# rapidshark-motor-connector-mk-1_0.net
KiCad netlist of a schematic drawn in EAGLE
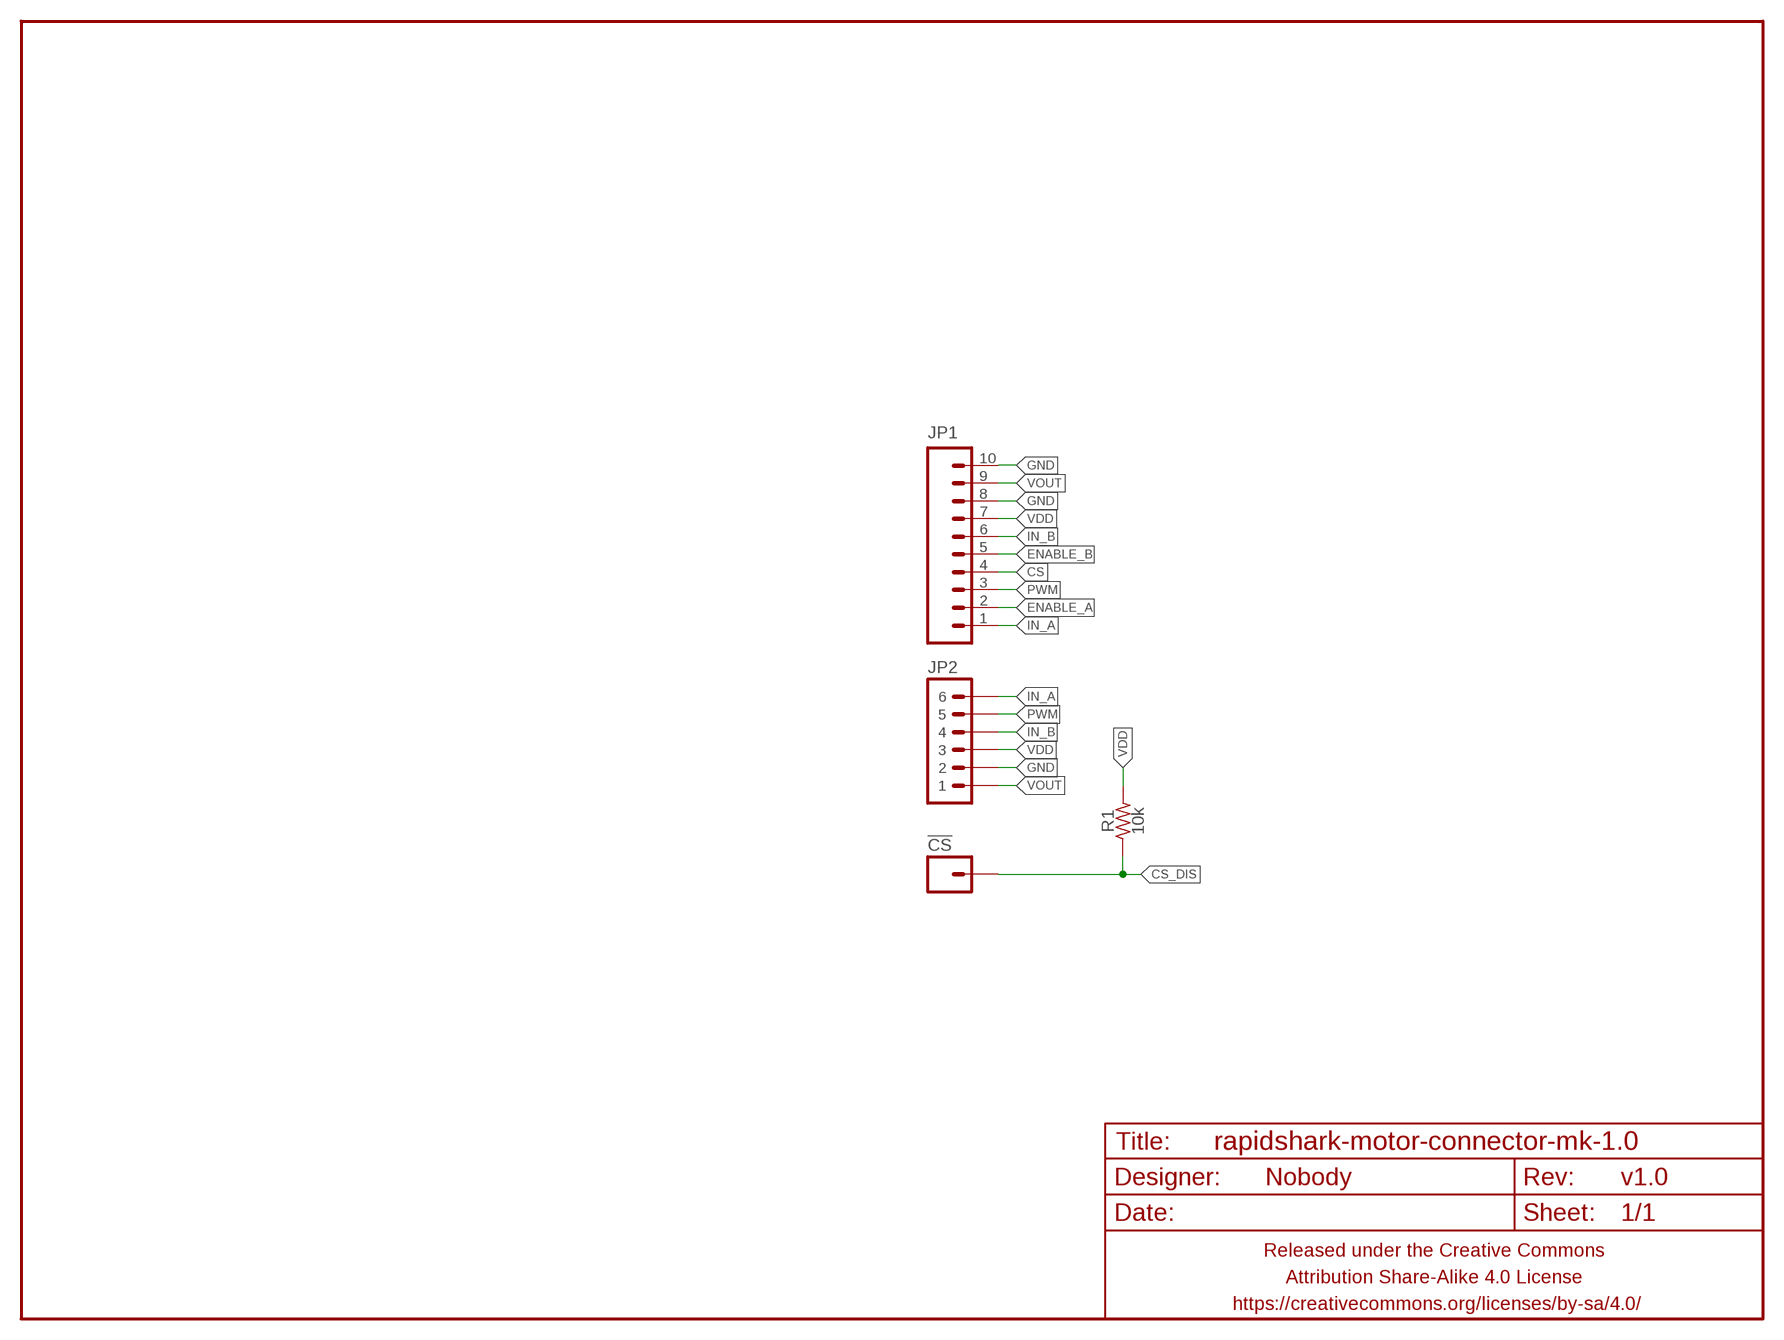
[diagram p0: schematic, sheet 1]

(export (version "E")
  (design (tool "Eeschema 10.0.6"))
  (components
    (comp (ref "!CS")
      (value "M01PTH")
      (footprint "eagle-import:1X01")
      (libsource (lib "eagle-import") (part "M01PTH"))
    )
    (comp (ref "FRAME1")
      (value "FRAME-LETTERNO_PACKAGE")
      (footprint "eagle-import:DUMMY")
      (fields (field (name "VERSION") "v1.0") (field (name "DESIGNER") "Nobody"))
      (libsource (lib "eagle-import") (part "FRAME-LETTERNO_PACKAGE"))
    )
    (comp (ref "JP1")
      (value "M10PTH")
      (footprint "eagle-import:1X10")
      (libsource (lib "eagle-import") (part "M10PTH"))
    )
    (comp (ref "JP2")
      (value "M06JST-PH-PTH-RA")
      (footprint "eagle-import:JST-6-PH-RA-PTH")
      (libsource (lib "eagle-import") (part "M06JST-PH-PTH-RA"))
    )
    (comp (ref "R1")
      (value "10k")
      (footprint "eagle-import:RESISTOR-AXIAL-PTH-6.35MM")
      (libsource (lib "eagle-import") (part "RESISTORPTH-AXIAL-6.35MM"))
    )
  )
  (nets
    (net (code "1") (name "CS") (class "Default")
      (node (ref "JP1") (pin "4") (pinfunction "4_4") (pintype "passive"))
    )
    (net (code "2") (name "CS_DIS") (class "Default")
      (node (ref "!CS") (pin "1") (pinfunction "1_1") (pintype "passive"))
      (node (ref "R1") (pin "P$1") (pinfunction "1_P$1") (pintype "passive"))
    )
    (net (code "3") (name "ENABLE_A") (class "Default")
      (node (ref "JP1") (pin "2") (pinfunction "2_2") (pintype "passive"))
    )
    (net (code "4") (name "ENABLE_B") (class "Default")
      (node (ref "JP1") (pin "5") (pinfunction "5_5") (pintype "passive"))
    )
    (net (code "5") (name "GND") (class "Default")
      (node (ref "JP1") (pin "10") (pinfunction "10_10") (pintype "passive"))
      (node (ref "JP1") (pin "8") (pinfunction "8_8") (pintype "passive"))
      (node (ref "JP2") (pin "2") (pinfunction "2_2") (pintype "passive"))
    )
    (net (code "6") (name "IN_A") (class "Default")
      (node (ref "JP1") (pin "1") (pinfunction "1_1") (pintype "passive"))
      (node (ref "JP2") (pin "6") (pinfunction "6_6") (pintype "passive"))
    )
    (net (code "7") (name "IN_B") (class "Default")
      (node (ref "JP1") (pin "6") (pinfunction "6_6") (pintype "passive"))
      (node (ref "JP2") (pin "4") (pinfunction "4_4") (pintype "passive"))
    )
    (net (code "8") (name "PWM") (class "Default")
      (node (ref "JP1") (pin "3") (pinfunction "3_3") (pintype "passive"))
      (node (ref "JP2") (pin "5") (pinfunction "5_5") (pintype "passive"))
    )
    (net (code "9") (name "VDD") (class "Default")
      (node (ref "JP1") (pin "7") (pinfunction "7_7") (pintype "passive"))
      (node (ref "JP2") (pin "3") (pinfunction "3_3") (pintype "passive"))
      (node (ref "R1") (pin "P$2") (pinfunction "2_P$2") (pintype "passive"))
    )
    (net (code "10") (name "VOUT") (class "Default")
      (node (ref "JP1") (pin "9") (pinfunction "9_9") (pintype "passive"))
      (node (ref "JP2") (pin "1") (pinfunction "1_1") (pintype "passive"))
    )
  )
)
